# Communications.net
KiCad netlist of a schematic drawn in Altium Designer
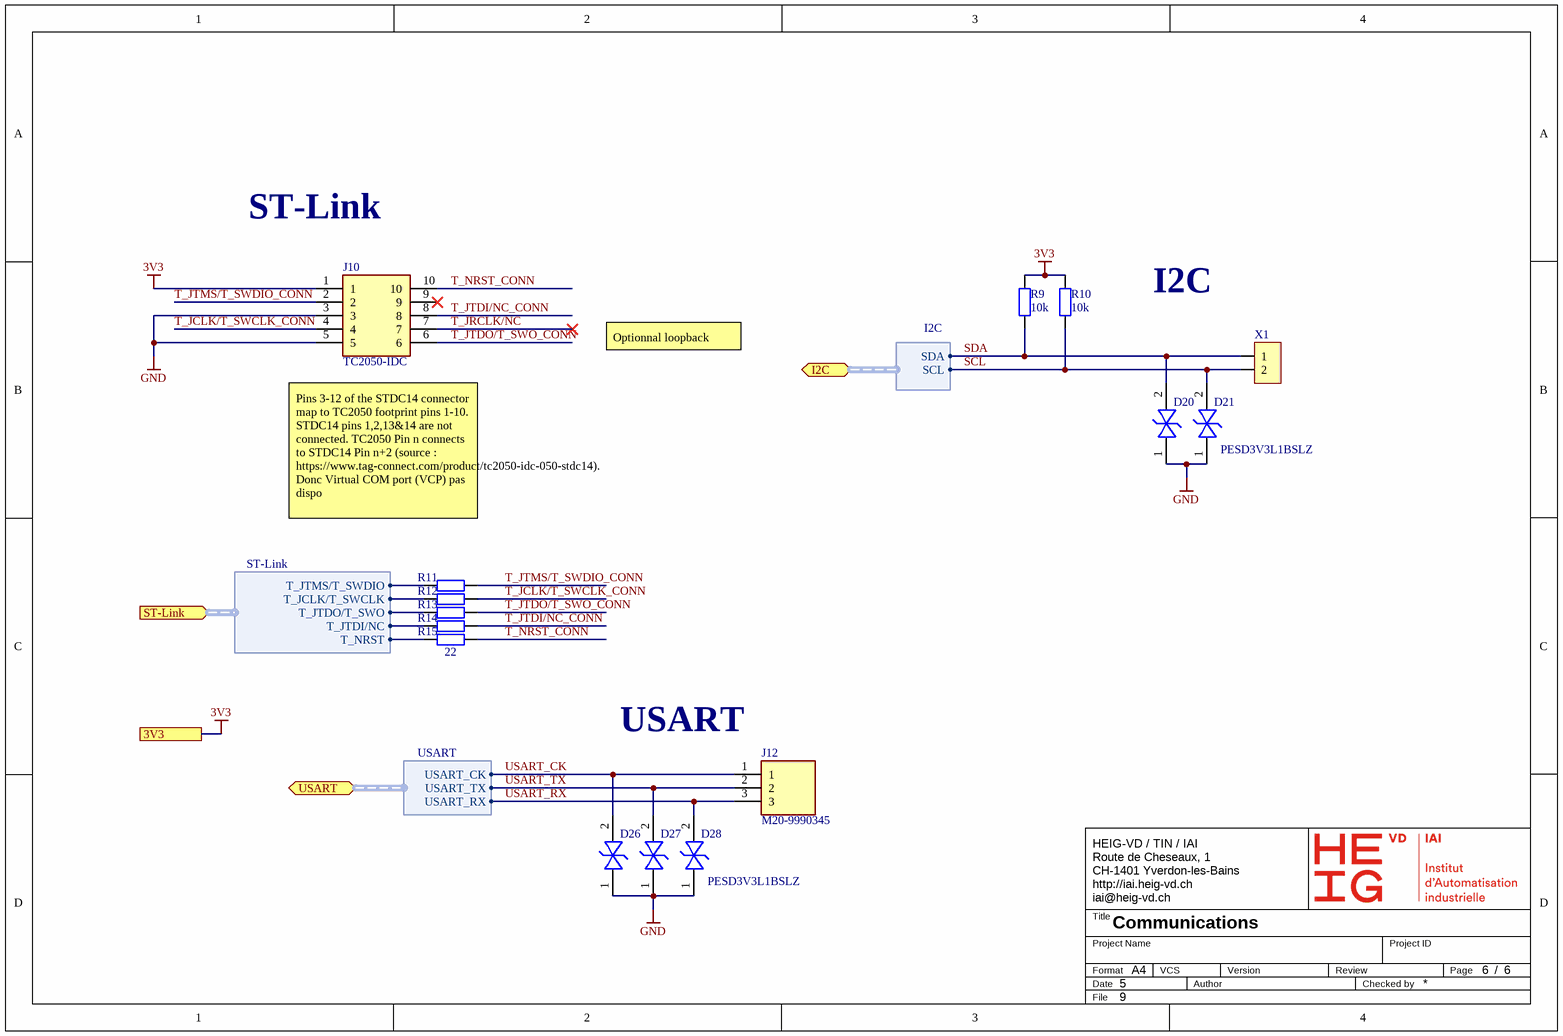
[diagram p0: Communications.SchDoc]

(export (version "E")
  (design (tool "Eeschema 10.0.6"))
  (components
    (comp (ref "D20")
      (value "PESD3V3L1BSLZ")
      (footprint "PESD3V3L1BSLZ")
      (description "Diode ESD (Bi-directional)")
      (fields (field (name "MOUSER PART NUMBER") "771-PESD3V3L1BSLZ"))
      (libsource (lib "Rainette") (part "PESD3V3L1BSLZ"))
    )
    (comp (ref "D21")
      (value "PESD3V3L1BSLZ")
      (footprint "PESD3V3L1BSLZ")
      (description "Diode ESD (Bi-directional)")
      (fields (field (name "MOUSER PART NUMBER") "771-PESD3V3L1BSLZ"))
      (libsource (lib "Rainette") (part "PESD3V3L1BSLZ"))
    )
    (comp (ref "D26")
      (value "PESD3V3L1BSLZ")
      (footprint "PESD3V3L1BSLZ")
      (description "Diode ESD (Bi-directional)")
      (fields (field (name "MOUSER PART NUMBER") "771-PESD3V3L1BSLZ"))
      (libsource (lib "Rainette") (part "PESD3V3L1BSLZ"))
    )
    (comp (ref "D27")
      (value "PESD3V3L1BSLZ")
      (footprint "PESD3V3L1BSLZ")
      (description "Diode ESD (Bi-directional)")
      (fields (field (name "MOUSER PART NUMBER") "771-PESD3V3L1BSLZ"))
      (libsource (lib "Rainette") (part "PESD3V3L1BSLZ"))
    )
    (comp (ref "D28")
      (value "PESD3V3L1BSLZ")
      (footprint "PESD3V3L1BSLZ")
      (description "Diode ESD (Bi-directional)")
      (fields (field (name "MOUSER PART NUMBER") "771-PESD3V3L1BSLZ"))
      (libsource (lib "Rainette") (part "PESD3V3L1BSLZ"))
    )
    (comp (ref "J10")
      (value "TC2050-IDC")
      (footprint "TC2050-IDC")
      (description "Connector")
      (libsource (lib "Rainette") (part "TC2050-IDC"))
    )
    (comp (ref "J12")
      (value "M20-9990345")
      (footprint "HDRV3W64P0X254_1X3_762X254X864P")
      (description "Connector")
      (fields (field (name "MOUSER PART NUMBER") "855-M20-9990345"))
      (libsource (lib "Rainette") (part "M20-9990345"))
    )
    (comp (ref "R9")
      (value "10k")
      (footprint "RESC1608X04N")
      (description "10 kOhms ±0.1% 0.1W, 1/10W Chip Resistor 0603 (1608 Metric) Thin Film")
      (fields (field (name "POWER") "100mW") (field (name "TOLERANCE") "0.1%"))
      (libsource (lib "") (part "Resistor_1"))
    )
    (comp (ref "R10")
      (value "10k")
      (footprint "RESC1608X04N")
      (description "10 kOhms ±0.1% 0.1W, 1/10W Chip Resistor 0603 (1608 Metric) Thin Film")
      (fields (field (name "POWER") "100mW") (field (name "TOLERANCE") "0.1%"))
      (libsource (lib "") (part "Resistor_1"))
    )
    (comp (ref "R11")
      (value "22")
      (footprint "RESC1608X04N")
      (description "22 Ohms ±1% 0.1W, 1/10W Chip Resistor 0603 (1608 Metric) Moisture Resistant Thick Film")
      (fields (field (name "POWER") "100mW") (field (name "TOLERANCE") "1%"))
      (libsource (lib "HEIG-VD Pro") (part "Resistor"))
    )
    (comp (ref "R12")
      (value "22")
      (footprint "RESC1608X04N")
      (description "22 Ohms ±1% 0.1W, 1/10W Chip Resistor 0603 (1608 Metric) Moisture Resistant Thick Film")
      (fields (field (name "POWER") "100mW") (field (name "TOLERANCE") "1%"))
      (libsource (lib "HEIG-VD Pro") (part "Resistor"))
    )
    (comp (ref "R13")
      (value "22")
      (footprint "RESC1608X04N")
      (description "22 Ohms ±1% 0.1W, 1/10W Chip Resistor 0603 (1608 Metric) Moisture Resistant Thick Film")
      (fields (field (name "POWER") "100mW") (field (name "TOLERANCE") "1%"))
      (libsource (lib "HEIG-VD Pro") (part "Resistor"))
    )
    (comp (ref "R14")
      (value "22")
      (footprint "RESC1608X04N")
      (description "22 Ohms ±1% 0.1W, 1/10W Chip Resistor 0603 (1608 Metric) Moisture Resistant Thick Film")
      (fields (field (name "POWER") "100mW") (field (name "TOLERANCE") "1%"))
      (libsource (lib "HEIG-VD Pro") (part "Resistor"))
    )
    (comp (ref "R15")
      (value "22")
      (footprint "RESC1608X04N")
      (description "22 Ohms ±1% 0.1W, 1/10W Chip Resistor 0603 (1608 Metric) Moisture Resistant Thick Film")
      (fields (field (name "POWER") "100mW") (field (name "TOLERANCE") "1%"))
      (libsource (lib "HEIG-VD Pro") (part "Resistor"))
    )
    (comp (ref "X1")
      (value "CONN HEADER VERT 2POS 2.54MM")
      (footprint "CONN HEADER VERT 2POS 2.54MM")
      (description "Connector Header Through Hole 2 position 0.100\" (2.54mm)")
      (libsource (lib "HEIG-VD Pro") (part "CONN HEADER VERT 2POS 2.54MM"))
    )
  )
  (nets
    (net (code "4") (name "/SCL") (class "Default")
      (node (ref "D21") (pin "2") (pinfunction "K2_2") (pintype "passive"))
      (node (ref "R10") (pin "1") (pinfunction "1_1") (pintype "passive"))
      (node (ref "X1") (pin "2") (pinfunction "2_2") (pintype "passive"))
    )
    (net (code "5") (name "/SDA") (class "Default")
      (node (ref "D20") (pin "2") (pinfunction "K2_2") (pintype "passive"))
      (node (ref "R9") (pin "1") (pinfunction "1_1") (pintype "passive"))
      (node (ref "X1") (pin "1") (pinfunction "1_1") (pintype "passive"))
    )
    (net (code "6") (name "/T_JCLK{slash}T_SWCLK") (class "Default")
      (node (ref "R12") (pin "1") (pinfunction "1_1") (pintype "passive"))
    )
    (net (code "7") (name "/T_JCLK{slash}T_SWCLK_CONN") (class "Default")
      (node (ref "J10") (pin "4") (pinfunction "4_4") (pintype "passive"))
      (node (ref "R12") (pin "2") (pinfunction "2_2") (pintype "passive"))
    )
    (net (code "8") (name "/T_JRCLK{slash}NC") (class "Default")
      (node (ref "J10") (pin "7") (pinfunction "7_7") (pintype "passive+no_connect"))
    )
    (net (code "9") (name "/T_JTDI{slash}NC") (class "Default")
      (node (ref "R14") (pin "1") (pinfunction "1_1") (pintype "passive"))
    )
    (net (code "10") (name "/T_JTDI{slash}NC_CONN") (class "Default")
      (node (ref "J10") (pin "8") (pinfunction "8_8") (pintype "passive"))
      (node (ref "R14") (pin "2") (pinfunction "2_2") (pintype "passive"))
    )
    (net (code "11") (name "/T_JTDO{slash}T_SWO") (class "Default")
      (node (ref "R13") (pin "1") (pinfunction "1_1") (pintype "passive"))
    )
    (net (code "12") (name "/T_JTDO{slash}T_SWO_CONN") (class "Default")
      (node (ref "J10") (pin "6") (pinfunction "6_6") (pintype "passive"))
      (node (ref "R13") (pin "2") (pinfunction "2_2") (pintype "passive"))
    )
    (net (code "13") (name "/T_JTMS{slash}T_SWDIO") (class "Default")
      (node (ref "R11") (pin "1") (pinfunction "1_1") (pintype "passive"))
    )
    (net (code "14") (name "/T_JTMS{slash}T_SWDIO_CONN") (class "Default")
      (node (ref "J10") (pin "2") (pinfunction "2_2") (pintype "passive"))
      (node (ref "R11") (pin "2") (pinfunction "2_2") (pintype "passive"))
    )
    (net (code "15") (name "/T_NRST") (class "Default")
      (node (ref "R15") (pin "1") (pinfunction "1_1") (pintype "passive"))
    )
    (net (code "16") (name "/T_NRST_CONN") (class "Default")
      (node (ref "J10") (pin "10") (pinfunction "10_10") (pintype "passive"))
      (node (ref "R15") (pin "2") (pinfunction "2_2") (pintype "passive"))
    )
    (net (code "17") (name "/USART_CK") (class "Default")
      (node (ref "D26") (pin "2") (pinfunction "K2_2") (pintype "passive"))
      (node (ref "J12") (pin "1") (pinfunction "1_1") (pintype "passive"))
    )
    (net (code "18") (name "/USART_RX") (class "Default")
      (node (ref "D28") (pin "2") (pinfunction "K2_2") (pintype "passive"))
      (node (ref "J12") (pin "3") (pinfunction "3_3") (pintype "passive"))
    )
    (net (code "19") (name "/USART_TX") (class "Default")
      (node (ref "D27") (pin "2") (pinfunction "K2_2") (pintype "passive"))
      (node (ref "J12") (pin "2") (pinfunction "2_2") (pintype "passive"))
    )
    (net (code "23") (name "3V3") (class "Default")
      (node (ref "J10") (pin "1") (pinfunction "1_1") (pintype "passive"))
      (node (ref "R10") (pin "2") (pinfunction "2_2") (pintype "passive"))
      (node (ref "R9") (pin "2") (pinfunction "2_2") (pintype "passive"))
    )
    (net (code "24") (name "GND") (class "Default")
      (node (ref "D20") (pin "1") (pinfunction "K1_1") (pintype "passive"))
      (node (ref "D21") (pin "1") (pinfunction "K1_1") (pintype "passive"))
      (node (ref "D26") (pin "1") (pinfunction "K1_1") (pintype "passive"))
      (node (ref "D27") (pin "1") (pinfunction "K1_1") (pintype "passive"))
      (node (ref "D28") (pin "1") (pinfunction "K1_1") (pintype "passive"))
      (node (ref "J10") (pin "3") (pinfunction "3_3") (pintype "passive"))
      (node (ref "J10") (pin "5") (pinfunction "5_5") (pintype "passive"))
    )
    (net (code "25") (name "unconnected-(J10-Pad9)") (class "Default")
      (node (ref "J10") (pin "9") (pinfunction "9_9") (pintype "passive+no_connect"))
    )
  )
)
